# PWR_LTC7150S.net
KiCad netlist of a schematic drawn in Altium Designer
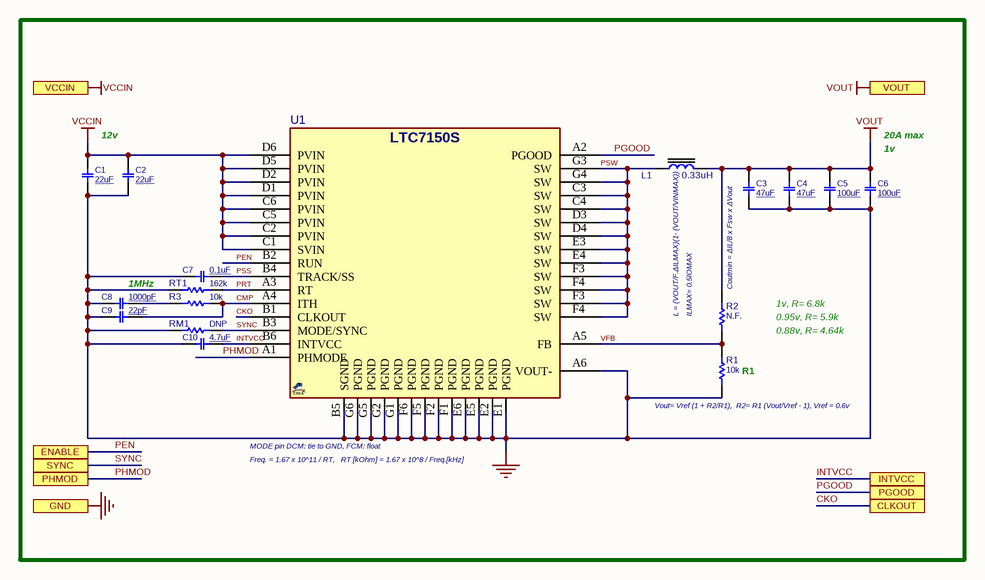
[diagram p0: PWR_LTC7150S.SchDoc]

(export (version "E")
  (design (tool "Eeschema 10.0.6"))
  (components
    (comp (ref "C1")
      (value "22uF")
      (footprint "C1206")
      (description "CAP, MLCC")
      (libsource (lib "passive_smd") (part "CAP_SMD_MLCC"))
    )
    (comp (ref "C2")
      (value "22uF")
      (footprint "C1206")
      (description "CAP, MLCC")
      (libsource (lib "passive_smd") (part "CAP_SMD_MLCC"))
    )
    (comp (ref "C3")
      (value "47uF")
      (footprint "C0805")
      (description "CAP, MLCC")
      (libsource (lib "passive_smd") (part "CAP_SMD_MLCC"))
    )
    (comp (ref "C4")
      (value "47uF")
      (footprint "C0805")
      (description "CAP, MLCC")
      (libsource (lib "passive_smd") (part "CAP_SMD_MLCC"))
    )
    (comp (ref "C5")
      (value "100uF")
      (footprint "C0805")
      (description "CAP, MLCC")
      (libsource (lib "passive_smd") (part "CAP_SMD_MLCC"))
    )
    (comp (ref "C6")
      (value "100uF")
      (footprint "C0805")
      (description "CAP, MLCC")
      (libsource (lib "passive_smd") (part "CAP_SMD_MLCC"))
    )
    (comp (ref "C7")
      (value "0.1uF")
      (footprint "C0402")
      (description "CAP, MLCC")
      (libsource (lib "passive_smd") (part "CAP_SMD_MLCC"))
    )
    (comp (ref "C8")
      (value "1000pF")
      (footprint "C0402")
      (description "CAP, MLCC")
      (libsource (lib "passive_smd") (part "CAP_SMD_MLCC"))
    )
    (comp (ref "C9")
      (value "22pF")
      (footprint "C0402")
      (description "CAP, MLCC")
      (libsource (lib "passive_smd") (part "CAP_SMD_MLCC"))
    )
    (comp (ref "C10")
      (value "4.7uF")
      (footprint "C0402")
      (description "CAP, MLCC")
      (libsource (lib "passive_smd") (part "CAP_SMD_MLCC"))
    )
    (comp (ref "L1")
      (value "0.33uH")
      (footprint "L_7")
      (description "INDUCTOR, POWER, SMD")
      (fields (field (name "MANF_P#") "SRP7028A-R33M"))
      (libsource (lib "passive_smd") (part "INDPWR_SMD"))
    )
    (comp (ref "R1")
      (value "10k")
      (footprint "R0402")
      (description "RESISTOR, SMD")
      (libsource (lib "passive_smd") (part "RES_SMD"))
    )
    (comp (ref "R2")
      (value "N.F.")
      (footprint "R0402")
      (description "RESISTOR, SMD")
      (libsource (lib "passive_smd") (part "RES_SMD"))
    )
    (comp (ref "R3")
      (value "10k")
      (footprint "R0402")
      (description "RESISTOR, SMD")
      (libsource (lib "passive_smd") (part "RES_SMD"))
    )
    (comp (ref "RM1")
      (value "DNP")
      (footprint "R0402")
      (description "RESISTOR, SMD")
      (libsource (lib "passive_smd") (part "RES_SMD"))
    )
    (comp (ref "RT1")
      (value "162k")
      (footprint "R0402")
      (description "RESISTOR, SMD")
      (libsource (lib "passive_smd") (part "RES_SMD"))
    )
    (comp (ref "U1")
      (value "LTC7150S")
      (footprint "BGA80_42_5060")
      (description "REG, Switching, Buck, 3.1~20V, 20A, BGA-42")
      (fields (field (name "MANF") "Texas Instruments") (field (name "MANF_P#") "LTC7150SEY, LTC7150SIY"))
      (libsource (lib "ltc7150s") (part "VREG_LTC7150S_BGA"))
    )
  )
  (nets
    (net (code "1") (name "/CKO") (class "Default")
      (node (ref "U1") (pin "B1") (pinfunction "CLKOUT_B1") (pintype "passive"))
    )
    (net (code "2") (name "/CMP") (class "Default")
      (node (ref "C9") (pin "2") (pinfunction "2_2") (pintype "passive"))
      (node (ref "R3") (pin "2") (pinfunction "2_2") (pintype "passive"))
      (node (ref "U1") (pin "A4") (pinfunction "ITH_A4") (pintype "passive"))
    )
    (net (code "3") (name "/INTVCC") (class "Default")
      (node (ref "C10") (pin "2") (pinfunction "2_2") (pintype "passive"))
      (node (ref "U1") (pin "B6") (pinfunction "INTVCC_B6") (pintype "passive"))
    )
    (net (code "4") (name "/PEN") (class "Default")
      (node (ref "U1") (pin "B2") (pinfunction "RUN_B2") (pintype "passive"))
    )
    (net (code "5") (name "/PGOOD") (class "Default")
      (node (ref "U1") (pin "A2") (pinfunction "PGOOD_A2") (pintype "passive"))
    )
    (net (code "6") (name "/PHMOD") (class "Default")
      (node (ref "U1") (pin "A1") (pinfunction "PHMODE_A1") (pintype "passive"))
    )
    (net (code "7") (name "/PRT") (class "Default")
      (node (ref "RT1") (pin "2") (pinfunction "2_2") (pintype "passive"))
      (node (ref "U1") (pin "A3") (pinfunction "RT_A3") (pintype "passive"))
    )
    (net (code "8") (name "/PSS") (class "Default")
      (node (ref "C7") (pin "2") (pinfunction "2_2") (pintype "passive"))
      (node (ref "U1") (pin "B4") (pinfunction "TRACK/SS_B4") (pintype "passive"))
    )
    (net (code "9") (name "/PSW") (class "Default")
      (node (ref "L1") (pin "1") (pinfunction "1_1") (pintype "passive"))
      (node (ref "U1") (pin "C3") (pinfunction "SW_C3") (pintype "passive"))
      (node (ref "U1") (pin "C4") (pinfunction "SW_C4") (pintype "passive"))
      (node (ref "U1") (pin "D3") (pinfunction "SW_D3") (pintype "passive"))
      (node (ref "U1") (pin "D4") (pinfunction "SW_D4") (pintype "passive"))
      (node (ref "U1") (pin "E3") (pinfunction "SW_E3") (pintype "passive"))
      (node (ref "U1") (pin "E4") (pinfunction "SW_E4") (pintype "passive"))
      (node (ref "U1") (pin "F3") (pinfunction "SW_F3") (pintype "passive"))
      (node (ref "U1") (pin "F4") (pinfunction "SW_F4") (pintype "passive"))
      (node (ref "U1") (pin "G3") (pinfunction "SW_G3") (pintype "passive"))
      (node (ref "U1") (pin "G4") (pinfunction "SW_G4") (pintype "passive"))
    )
    (net (code "10") (name "/SYNC") (class "Default")
      (node (ref "RM1") (pin "2") (pinfunction "2_2") (pintype "passive"))
      (node (ref "U1") (pin "B3") (pinfunction "MODE/SYNC_B3") (pintype "passive"))
    )
    (net (code "11") (name "/VFB") (class "Default")
      (node (ref "R1") (pin "2") (pinfunction "2_2") (pintype "passive"))
      (node (ref "R2") (pin "1") (pinfunction "1_1") (pintype "passive"))
      (node (ref "U1") (pin "A5") (pinfunction "FB_A5") (pintype "passive"))
    )
    (net (code "12") (name "GND") (class "Default")
      (node (ref "C1") (pin "2") (pinfunction "2_2") (pintype "passive"))
      (node (ref "C10") (pin "1") (pinfunction "1_1") (pintype "passive"))
      (node (ref "C2") (pin "2") (pinfunction "2_2") (pintype "passive"))
      (node (ref "C3") (pin "2") (pinfunction "2_2") (pintype "passive"))
      (node (ref "C4") (pin "2") (pinfunction "2_2") (pintype "passive"))
      (node (ref "C5") (pin "2") (pinfunction "2_2") (pintype "passive"))
      (node (ref "C6") (pin "2") (pinfunction "2_2") (pintype "passive"))
      (node (ref "C7") (pin "1") (pinfunction "1_1") (pintype "passive"))
      (node (ref "C8") (pin "1") (pinfunction "1_1") (pintype "passive"))
      (node (ref "C9") (pin "1") (pinfunction "1_1") (pintype "passive"))
      (node (ref "R1") (pin "1") (pinfunction "1_1") (pintype "passive"))
      (node (ref "RM1") (pin "1") (pinfunction "1_1") (pintype "passive"))
      (node (ref "RT1") (pin "1") (pinfunction "1_1") (pintype "passive"))
      (node (ref "U1") (pin "A6") (pinfunction "VOUT-_A6") (pintype "passive"))
      (node (ref "U1") (pin "B5") (pinfunction "SGND_B5") (pintype "passive"))
      (node (ref "U1") (pin "E1") (pinfunction "PGND_E1") (pintype "passive"))
      (node (ref "U1") (pin "E2") (pinfunction "PGND_E2") (pintype "passive"))
      (node (ref "U1") (pin "E5") (pinfunction "PGND_E5") (pintype "passive"))
      (node (ref "U1") (pin "E6") (pinfunction "PGND_E6") (pintype "passive"))
      (node (ref "U1") (pin "F1") (pinfunction "PGND_F1") (pintype "passive"))
      (node (ref "U1") (pin "F2") (pinfunction "PGND_F2") (pintype "passive"))
      (node (ref "U1") (pin "F5") (pinfunction "PGND_F5") (pintype "passive"))
      (node (ref "U1") (pin "F6") (pinfunction "PGND_F6") (pintype "passive"))
      (node (ref "U1") (pin "G1") (pinfunction "PGND_G1") (pintype "passive"))
      (node (ref "U1") (pin "G2") (pinfunction "PGND_G2") (pintype "passive"))
      (node (ref "U1") (pin "G5") (pinfunction "PGND_G5") (pintype "passive"))
      (node (ref "U1") (pin "G6") (pinfunction "PGND_G6") (pintype "passive"))
    )
    (net (code "13") (name "Net-(C8-Pad2)") (class "Default")
      (node (ref "C8") (pin "2") (pinfunction "2_2") (pintype "passive"))
      (node (ref "R3") (pin "1") (pinfunction "1_1") (pintype "passive"))
    )
    (net (code "14") (name "VCCIN") (class "Default")
      (node (ref "C1") (pin "1") (pinfunction "1_1") (pintype "passive"))
      (node (ref "C2") (pin "1") (pinfunction "1_1") (pintype "passive"))
      (node (ref "U1") (pin "C1") (pinfunction "SVIN_C1") (pintype "passive"))
      (node (ref "U1") (pin "C2") (pinfunction "PVIN_C2") (pintype "passive"))
      (node (ref "U1") (pin "C5") (pinfunction "PVIN_C5") (pintype "passive"))
      (node (ref "U1") (pin "C6") (pinfunction "PVIN_C6") (pintype "passive"))
      (node (ref "U1") (pin "D1") (pinfunction "PVIN_D1") (pintype "passive"))
      (node (ref "U1") (pin "D2") (pinfunction "PVIN_D2") (pintype "passive"))
      (node (ref "U1") (pin "D5") (pinfunction "PVIN_D5") (pintype "passive"))
      (node (ref "U1") (pin "D6") (pinfunction "PVIN_D6") (pintype "passive"))
    )
    (net (code "15") (name "VOUT") (class "Default")
      (node (ref "C3") (pin "1") (pinfunction "1_1") (pintype "passive"))
      (node (ref "C4") (pin "1") (pinfunction "1_1") (pintype "passive"))
      (node (ref "C5") (pin "1") (pinfunction "1_1") (pintype "passive"))
      (node (ref "C6") (pin "1") (pinfunction "1_1") (pintype "passive"))
      (node (ref "L1") (pin "2") (pinfunction "2_2") (pintype "passive"))
      (node (ref "R2") (pin "2") (pinfunction "2_2") (pintype "passive"))
    )
  )
)
